# esp-firework-firing-system-hw1_1.net
KiCad netlist of a schematic drawn in EasyEDA
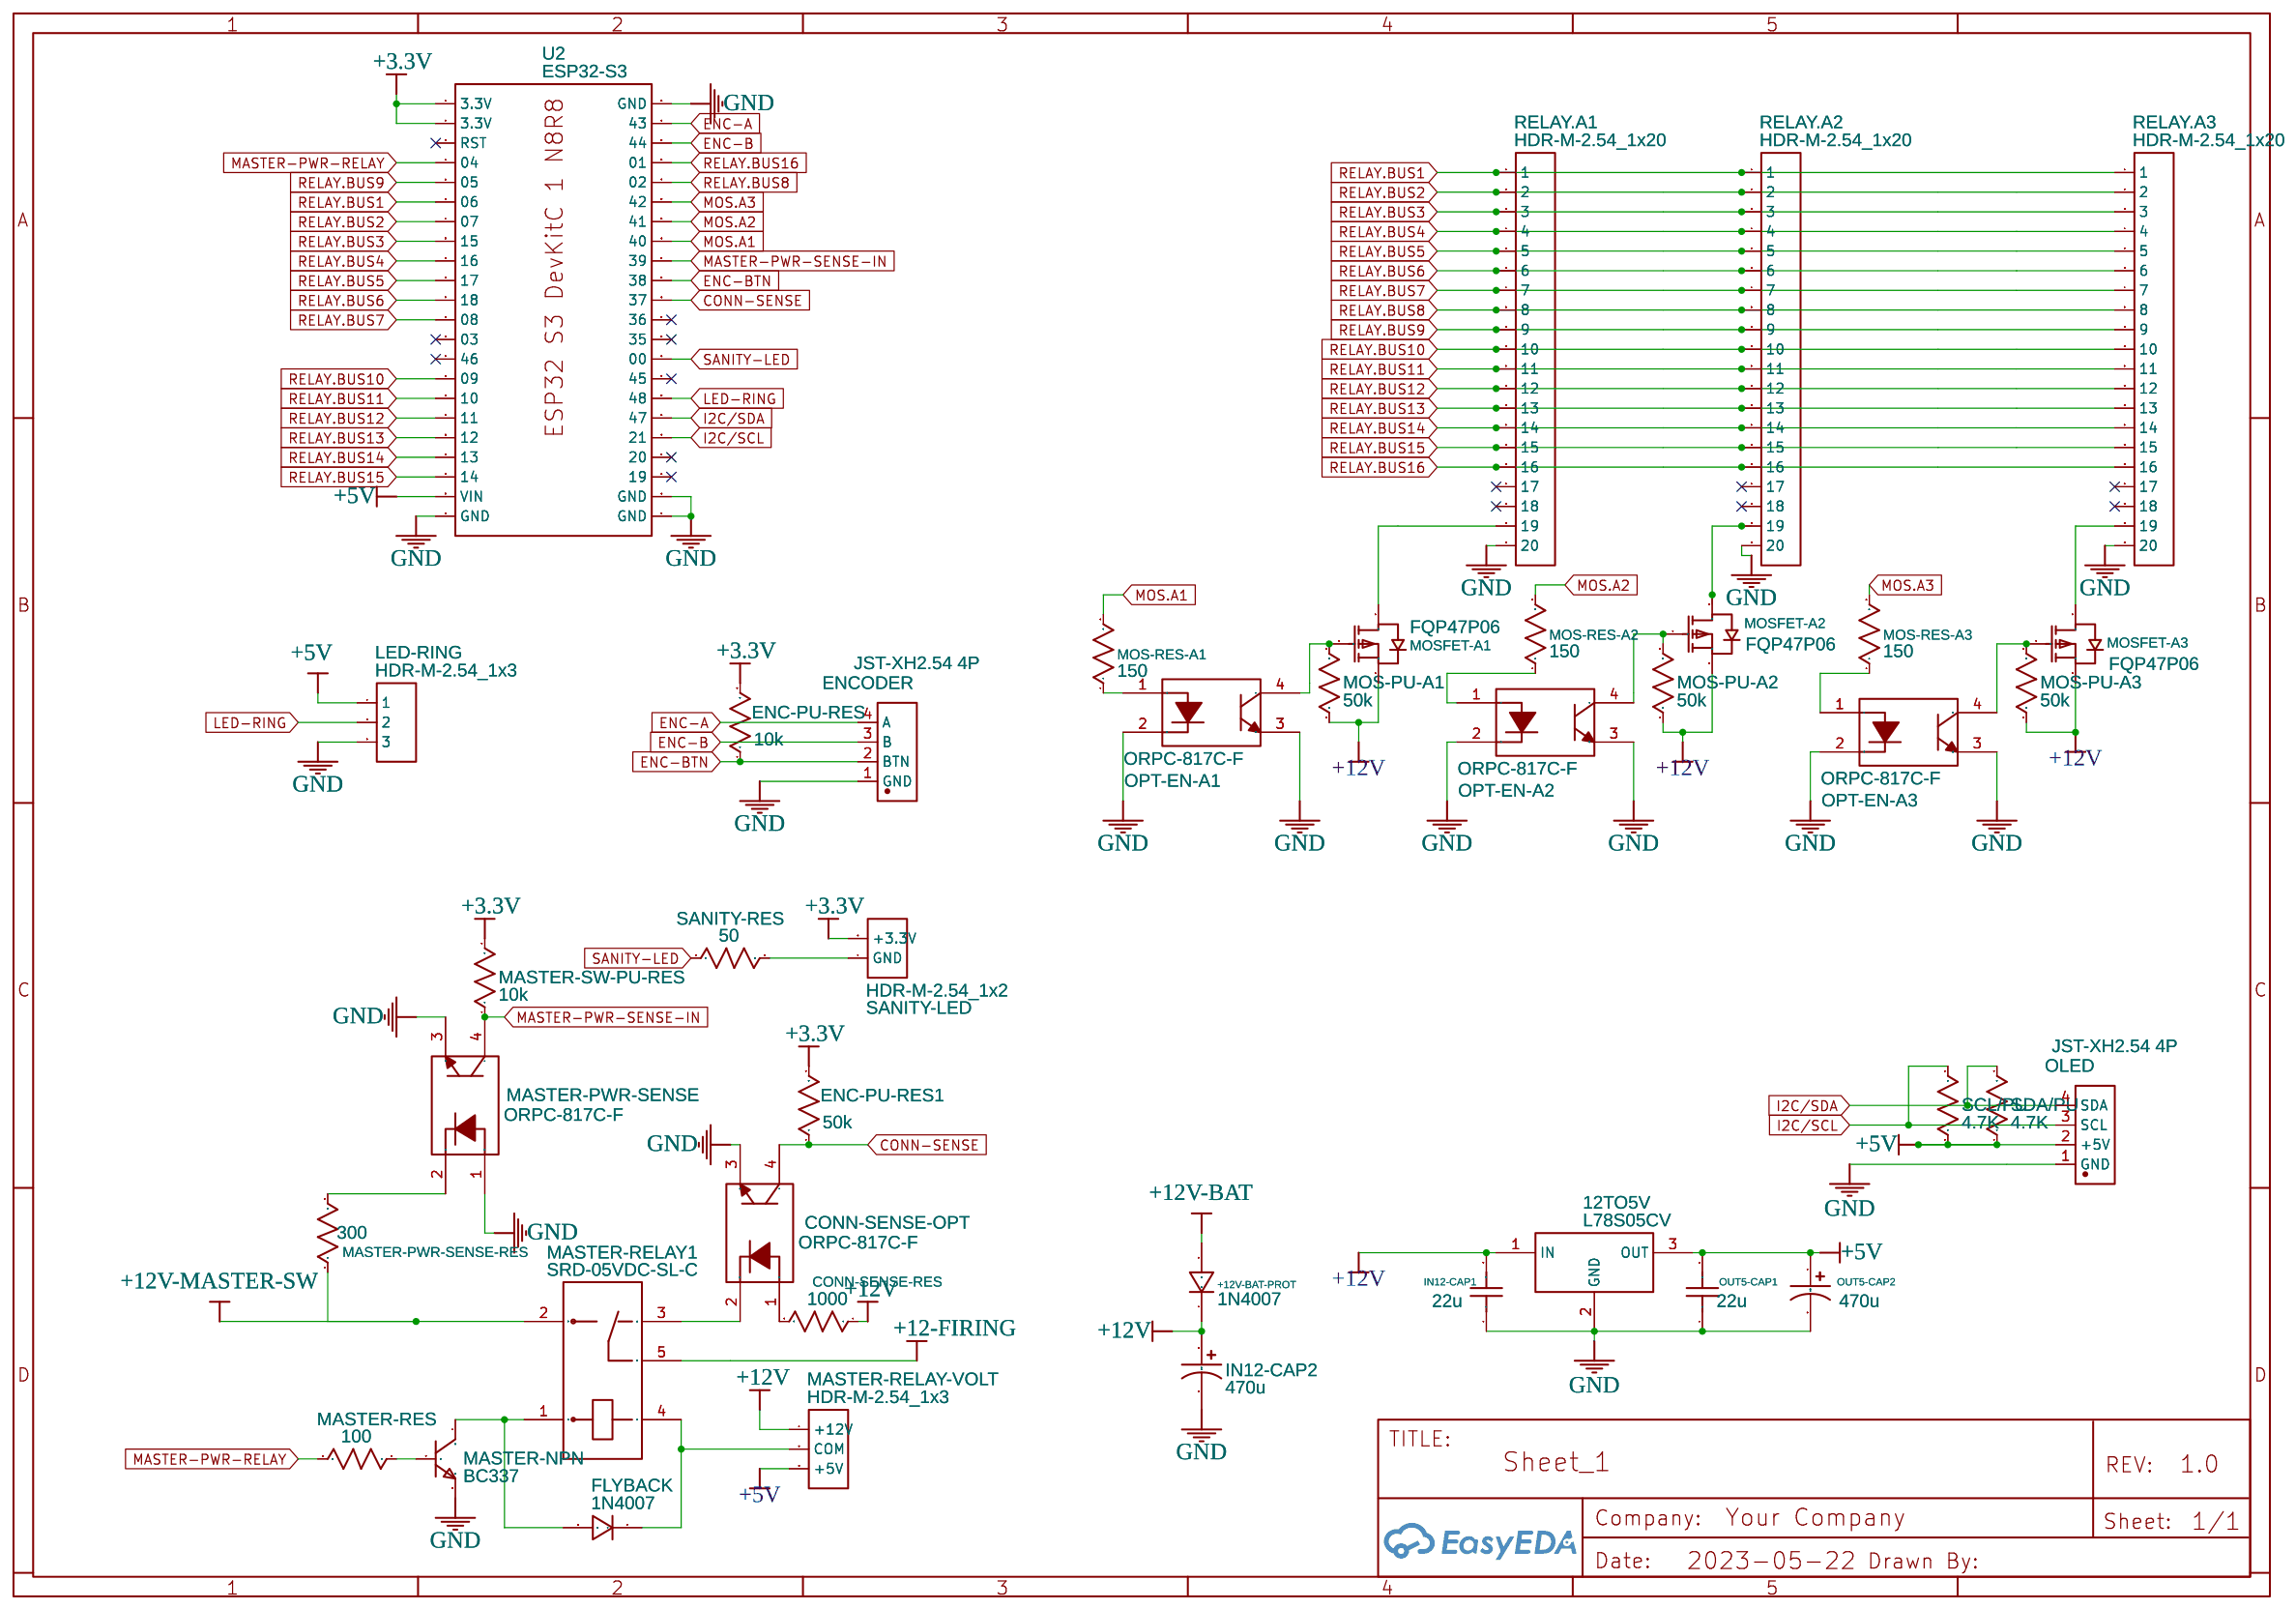
[diagram p0: schematic sheet]

(export (version "E")
  (design (tool "Eeschema 10.0.6"))
  (components
    (comp (ref "+12V-BAT-PROT")
      (value "1N4007")
      (fields (field (name "BOM_Supplier Part") "C106903"))
      (libsource (lib "") (part "1N4007_1"))
    )
    (comp (ref "12TO5V")
      (value "L78S05CV")
      (fields (field (name "BOM_Supplier Part") "C33043"))
      (libsource (lib "") (part "L78S05CV"))
    )
    (comp (ref "CONN-SENSE-OPT")
      (value "ORPC-817C-F")
      (fields (field (name "BOM_Supplier Part") "C2842770"))
      (libsource (lib "") (part "ORPC-817C-F_1"))
    )
    (comp (ref "CONN-SENSE-RES") (value "1000") (libsource (lib "") (part "R_AXIAL-0.3_US")))
    (comp (ref "ENC-PU-RES") (value "10k") (libsource (lib "") (part "R_AXIAL-0.3_US_3")))
    (comp (ref "ENC-PU-RES1") (value "50k") (libsource (lib "") (part "R_AXIAL-0.3_US_3")))
    (comp (ref "ENCODER") (value "JST-XH2.54 4P") (libsource (lib "") (part "JST-XH2.54 4P_1")))
    (comp (ref "FLYBACK")
      (value "1N4007")
      (fields (field (name "BOM_Supplier Part") "C106903"))
      (libsource (lib "") (part "1N4007"))
    )
    (comp (ref "IN12-CAP1") (value "22u") (libsource (lib "") (part "C_RAD-0.1_US_1")))
    (comp (ref "IN12-CAP2") (value "470u") (libsource (lib "") (part "CE_TH_D6.3×F2.5_US")))
    (comp (ref "LED-RING")
      (value "HDR-M-2.54_1x3")
      (fields (field (name "BOM_Supplier Part") "C180248"))
      (libsource (lib "") (part "HDR-M-2.54_1x3_1"))
    )
    (comp (ref "MASTER-NPN") (value "BC337") (libsource (lib "") (part "BC337")))
    (comp (ref "MASTER-PWR-SENSE")
      (value "ORPC-817C-F")
      (fields (field (name "BOM_Supplier Part") "C2842770"))
      (libsource (lib "") (part "ORPC-817C-F_2"))
    )
    (comp (ref "MASTER-PWR-SENSE-RES") (value "300") (libsource (lib "") (part "R_AXIAL-0.3_US_7")))
    (comp (ref "MASTER-RELAY-VOLT")
      (value "HDR-M-2.54_1x3")
      (fields (field (name "BOM_Supplier Part") "C180248"))
      (libsource (lib "") (part "HDR-M-2.54_1x3"))
    )
    (comp (ref "MASTER-RELAY1")
      (value "SRD-05VDC-SL-C")
      (fields (field (name "BOM_Supplier Part") "C35449"))
      (libsource (lib "") (part "SRD-05VDC-SL-C"))
    )
    (comp (ref "MASTER-RES") (value "100") (libsource (lib "") (part "R_AXIAL-0.3_US_6")))
    (comp (ref "MASTER-SW-PU-RES") (value "10k") (libsource (lib "") (part "R_AXIAL-0.3_US_1")))
    (comp (ref "MOS-PU-A1") (value "50k") (libsource (lib "") (part "R_AXIAL-0.3_US_2")))
    (comp (ref "MOS-PU-A2") (value "50k") (libsource (lib "") (part "R_AXIAL-0.3_US_2")))
    (comp (ref "MOS-PU-A3") (value "50k") (libsource (lib "") (part "R_AXIAL-0.3_US_2")))
    (comp (ref "MOS-RES-A1") (value "150") (libsource (lib "") (part "R_AXIAL-0.3_US_5")))
    (comp (ref "MOS-RES-A2") (value "150") (libsource (lib "") (part "R_AXIAL-0.3_US_5")))
    (comp (ref "MOS-RES-A3") (value "150") (libsource (lib "") (part "R_AXIAL-0.3_US_5")))
    (comp (ref "MOSFET-A1")
      (value "FQP47P06")
      (fields (field (name "BOM_Supplier Part") "C462765"))
      (libsource (lib "") (part "FQP47P06"))
    )
    (comp (ref "MOSFET-A2")
      (value "FQP47P06")
      (fields (field (name "BOM_Supplier Part") "C462765"))
      (libsource (lib "") (part "FQP47P06"))
    )
    (comp (ref "MOSFET-A3")
      (value "FQP47P06")
      (fields (field (name "BOM_Supplier Part") "C462765"))
      (libsource (lib "") (part "FQP47P06"))
    )
    (comp (ref "OLED") (value "JST-XH2.54 4P") (libsource (lib "") (part "JST-XH2.54 4P")))
    (comp (ref "OPT-EN-A1")
      (value "ORPC-817C-F")
      (fields (field (name "BOM_Supplier Part") "C2842770"))
      (libsource (lib "") (part "ORPC-817C-F"))
    )
    (comp (ref "OPT-EN-A2")
      (value "ORPC-817C-F")
      (fields (field (name "BOM_Supplier Part") "C2842770"))
      (libsource (lib "") (part "ORPC-817C-F"))
    )
    (comp (ref "OPT-EN-A3")
      (value "ORPC-817C-F")
      (fields (field (name "BOM_Supplier Part") "C2842770"))
      (libsource (lib "") (part "ORPC-817C-F"))
    )
    (comp (ref "OUT5-CAP1") (value "22u") (libsource (lib "") (part "C_RAD-0.1_US")))
    (comp (ref "OUT5-CAP2") (value "470u") (libsource (lib "") (part "CE_TH_D6.3×F2.5_US_1")))
    (comp (ref "RELAY.A1")
      (value "HDR-M-2.54_1x20")
      (fields (field (name "BOM_Supplier Part") "C50981"))
      (libsource (lib "") (part "HDR-M-2.54_1x20"))
    )
    (comp (ref "RELAY.A2")
      (value "HDR-M-2.54_1x20")
      (fields (field (name "BOM_Supplier Part") "C50981"))
      (libsource (lib "") (part "HDR-M-2.54_1x20"))
    )
    (comp (ref "RELAY.A3")
      (value "HDR-M-2.54_1x20")
      (fields (field (name "BOM_Supplier Part") "C50981"))
      (libsource (lib "") (part "HDR-M-2.54_1x20"))
    )
    (comp (ref "SANITY-LED")
      (value "HDR-M-2.54_1x2")
      (fields (field (name "BOM_Supplier Part") "C124375"))
      (libsource (lib "") (part "HDR-M-2.54_1x2"))
    )
    (comp (ref "SANITY-RES") (value "50") (libsource (lib "") (part "R_AXIAL-0.3_US_9")))
    (comp (ref "SCL/PU") (value "4.7K") (libsource (lib "") (part "R_AXIAL-0.3_US_4")))
    (comp (ref "SDA/PU") (value "4.7K") (libsource (lib "") (part "R_AXIAL-0.3_US_8")))
    (comp (ref "U2") (value "ESP32-S3") (libsource (lib "") (part "ESP32-S3")))
  )
  (nets
    (net (code "1") (name "+3.3V") (class "Default")
      (node (ref "ENC-PU-RES") (pin "2") (pinfunction "2_2") (pintype "unspecified"))
      (node (ref "ENC-PU-RES1") (pin "2") (pinfunction "2_2") (pintype "unspecified"))
      (node (ref "MASTER-SW-PU-RES") (pin "2") (pinfunction "2_2") (pintype "unspecified"))
      (node (ref "SANITY-LED") (pin "2") (pinfunction "+3.3V_2") (pintype "unspecified"))
      (node (ref "U2") (pin "1") (pinfunction "3.3V_1") (pintype "unspecified"))
      (node (ref "U2") (pin "2") (pinfunction "3.3V_2") (pintype "unspecified"))
    )
    (net (code "2") (name "+5V") (class "Default")
      (node (ref "12TO5V") (pin "3") (pinfunction "OUT_3") (pintype "passive"))
      (node (ref "LED-RING") (pin "1") (pinfunction "1_1") (pintype "input"))
      (node (ref "MASTER-RELAY-VOLT") (pin "3") (pinfunction "+5V_3") (pintype "input"))
      (node (ref "OLED") (pin "2") (pinfunction "+5V_2") (pintype "unspecified"))
      (node (ref "OUT5-CAP1") (pin "2") (pinfunction "2_2") (pintype "unspecified"))
      (node (ref "OUT5-CAP2") (pin "1") (pinfunction "1_1") (pintype "unspecified"))
      (node (ref "SCL/PU") (pin "1") (pinfunction "1_1") (pintype "unspecified"))
      (node (ref "SDA/PU") (pin "1") (pinfunction "1_1") (pintype "unspecified"))
      (node (ref "U2") (pin "21") (pinfunction "VIN_21") (pintype "unspecified"))
    )
    (net (code "3") (name "+12-FIRING") (class "Default")
      (node (ref "MASTER-RELAY1") (pin "5") (pinfunction "5_5") (pintype "input"))
    )
    (net (code "4") (name "+12V") (class "Default")
      (node (ref "+12V-BAT-PROT") (pin "1") (pinfunction "1_1") (pintype "unspecified"))
      (node (ref "12TO5V") (pin "1") (pinfunction "IN_1") (pintype "passive"))
      (node (ref "CONN-SENSE-RES") (pin "1") (pinfunction "1_1") (pintype "unspecified"))
      (node (ref "IN12-CAP1") (pin "2") (pinfunction "2_2") (pintype "unspecified"))
      (node (ref "IN12-CAP2") (pin "1") (pinfunction "1_1") (pintype "unspecified"))
      (node (ref "MASTER-RELAY-VOLT") (pin "1") (pinfunction "+12V_1") (pintype "input"))
      (node (ref "MOS-PU-A1") (pin "1") (pinfunction "1_1") (pintype "unspecified"))
      (node (ref "MOS-PU-A2") (pin "1") (pinfunction "1_1") (pintype "unspecified"))
      (node (ref "MOS-PU-A3") (pin "1") (pinfunction "1_1") (pintype "unspecified"))
      (node (ref "MOSFET-A1") (pin "3") (pinfunction "S_3") (pintype "unspecified"))
      (node (ref "MOSFET-A2") (pin "3") (pinfunction "S_3") (pintype "unspecified"))
      (node (ref "MOSFET-A3") (pin "3") (pinfunction "S_3") (pintype "unspecified"))
    )
    (net (code "5") (name "+12V-BAT") (class "Default")
      (node (ref "+12V-BAT-PROT") (pin "2") (pinfunction "2_2") (pintype "unspecified"))
    )
    (net (code "6") (name "+12V-MASTER-SW") (class "Default")
      (node (ref "MASTER-PWR-SENSE-RES") (pin "1") (pinfunction "1_1") (pintype "unspecified"))
      (node (ref "MASTER-RELAY1") (pin "2") (pinfunction "2_2") (pintype "input"))
    )
    (net (code "7") (name "CONN-SENSE") (class "Default")
      (node (ref "CONN-SENSE-OPT") (pin "4") (pinfunction "4_4") (pintype "unspecified"))
      (node (ref "ENC-PU-RES1") (pin "1") (pinfunction "1_1") (pintype "unspecified"))
      (node (ref "U2") (pin "33") (pinfunction "37_33") (pintype "unspecified"))
    )
    (net (code "8") (name "ENC-A") (class "Default")
      (node (ref "ENCODER") (pin "4") (pinfunction "A_4") (pintype "unspecified"))
      (node (ref "U2") (pin "24") (pinfunction "43_24") (pintype "unspecified"))
    )
    (net (code "9") (name "ENC-B") (class "Default")
      (node (ref "ENCODER") (pin "3") (pinfunction "B_3") (pintype "unspecified"))
      (node (ref "U2") (pin "25") (pinfunction "44_25") (pintype "unspecified"))
    )
    (net (code "10") (name "ENC-BTN") (class "Default")
      (node (ref "ENC-PU-RES") (pin "1") (pinfunction "1_1") (pintype "unspecified"))
      (node (ref "ENCODER") (pin "2") (pinfunction "BTN_2") (pintype "unspecified"))
      (node (ref "U2") (pin "32") (pinfunction "38_32") (pintype "unspecified"))
    )
    (net (code "11") (name "GND") (class "Default")
      (node (ref "12TO5V") (pin "2") (pinfunction "GND_2") (pintype "passive"))
      (node (ref "CONN-SENSE-OPT") (pin "3") (pinfunction "3_3") (pintype "unspecified"))
      (node (ref "ENCODER") (pin "1") (pinfunction "GND_1") (pintype "unspecified"))
      (node (ref "IN12-CAP1") (pin "1") (pinfunction "1_1") (pintype "unspecified"))
      (node (ref "IN12-CAP2") (pin "2") (pinfunction "2_2") (pintype "unspecified"))
      (node (ref "LED-RING") (pin "3") (pinfunction "3_3") (pintype "input"))
      (node (ref "MASTER-NPN") (pin "3") (pinfunction "E_3") (pintype "unspecified"))
      (node (ref "MASTER-PWR-SENSE") (pin "1") (pinfunction "1_1") (pintype "unspecified"))
      (node (ref "MASTER-PWR-SENSE") (pin "3") (pinfunction "3_3") (pintype "unspecified"))
      (node (ref "OLED") (pin "1") (pinfunction "GND_1") (pintype "unspecified"))
      (node (ref "OPT-EN-A1") (pin "2") (pinfunction "2_2") (pintype "unspecified"))
      (node (ref "OPT-EN-A1") (pin "3") (pinfunction "3_3") (pintype "unspecified"))
      (node (ref "OPT-EN-A2") (pin "2") (pinfunction "2_2") (pintype "unspecified"))
      (node (ref "OPT-EN-A2") (pin "3") (pinfunction "3_3") (pintype "unspecified"))
      (node (ref "OPT-EN-A3") (pin "2") (pinfunction "2_2") (pintype "unspecified"))
      (node (ref "OPT-EN-A3") (pin "3") (pinfunction "3_3") (pintype "unspecified"))
      (node (ref "OUT5-CAP1") (pin "1") (pinfunction "1_1") (pintype "unspecified"))
      (node (ref "OUT5-CAP2") (pin "2") (pinfunction "2_2") (pintype "unspecified"))
      (node (ref "RELAY.A1") (pin "20") (pinfunction "20_20") (pintype "unspecified"))
      (node (ref "RELAY.A2") (pin "20") (pinfunction "20_20") (pintype "unspecified"))
      (node (ref "RELAY.A3") (pin "20") (pinfunction "20_20") (pintype "unspecified"))
      (node (ref "U2") (pin "22") (pinfunction "GND_22") (pintype "unspecified"))
      (node (ref "U2") (pin "23") (pinfunction "GND_23") (pintype "unspecified"))
      (node (ref "U2") (pin "43") (pinfunction "GND_43") (pintype "unspecified"))
      (node (ref "U2") (pin "44") (pinfunction "GND_44") (pintype "unspecified"))
    )
    (net (code "12") (name "I2C{slash}SCL") (class "Default")
      (node (ref "OLED") (pin "3") (pinfunction "SCL_3") (pintype "unspecified"))
      (node (ref "SCL/PU") (pin "2") (pinfunction "2_2") (pintype "unspecified"))
      (node (ref "U2") (pin "40") (pinfunction "21_40") (pintype "unspecified"))
    )
    (net (code "13") (name "I2C{slash}SDA") (class "Default")
      (node (ref "OLED") (pin "4") (pinfunction "SDA_4") (pintype "unspecified"))
      (node (ref "SDA/PU") (pin "2") (pinfunction "2_2") (pintype "unspecified"))
      (node (ref "U2") (pin "39") (pinfunction "47_39") (pintype "unspecified"))
    )
    (net (code "14") (name "LED-RING") (class "Default")
      (node (ref "LED-RING") (pin "2") (pinfunction "2_2") (pintype "input"))
      (node (ref "U2") (pin "38") (pinfunction "48_38") (pintype "unspecified"))
    )
    (net (code "15") (name "MASTER-PWR-RELAY") (class "Default")
      (node (ref "MASTER-RES") (pin "2") (pinfunction "2_2") (pintype "unspecified"))
      (node (ref "U2") (pin "4") (pinfunction "04_4") (pintype "unspecified"))
    )
    (net (code "16") (name "MASTER-PWR-SENSE-IN") (class "Default")
      (node (ref "MASTER-PWR-SENSE") (pin "4") (pinfunction "4_4") (pintype "unspecified"))
      (node (ref "MASTER-SW-PU-RES") (pin "1") (pinfunction "1_1") (pintype "unspecified"))
      (node (ref "U2") (pin "31") (pinfunction "39_31") (pintype "unspecified"))
    )
    (net (code "17") (name "MOS.A1") (class "Default")
      (node (ref "MOS-RES-A1") (pin "2") (pinfunction "2_2") (pintype "unspecified"))
      (node (ref "U2") (pin "30") (pinfunction "40_30") (pintype "unspecified"))
    )
    (net (code "18") (name "MOS.A2") (class "Default")
      (node (ref "MOS-RES-A2") (pin "2") (pinfunction "2_2") (pintype "unspecified"))
      (node (ref "U2") (pin "29") (pinfunction "41_29") (pintype "unspecified"))
    )
    (net (code "19") (name "MOS.A3") (class "Default")
      (node (ref "MOS-RES-A3") (pin "2") (pinfunction "2_2") (pintype "unspecified"))
      (node (ref "U2") (pin "28") (pinfunction "42_28") (pintype "unspecified"))
    )
    (net (code "20") (name "Net-(CONN-SENSE-OPT-Pad1)") (class "Default")
      (node (ref "CONN-SENSE-OPT") (pin "1") (pinfunction "1_1") (pintype "unspecified"))
      (node (ref "CONN-SENSE-RES") (pin "2") (pinfunction "2_2") (pintype "unspecified"))
    )
    (net (code "21") (name "Net-(CONN-SENSE-OPT-Pad2)") (class "Default")
      (node (ref "CONN-SENSE-OPT") (pin "2") (pinfunction "2_2") (pintype "unspecified"))
      (node (ref "MASTER-RELAY1") (pin "3") (pinfunction "3_3") (pintype "input"))
    )
    (net (code "22") (name "Net-(MASTER-NPN-B)") (class "Default")
      (node (ref "MASTER-NPN") (pin "2") (pinfunction "B_2") (pintype "unspecified"))
      (node (ref "MASTER-RES") (pin "1") (pinfunction "1_1") (pintype "unspecified"))
    )
    (net (code "23") (name "Net-(MASTER-NPN-C)") (class "Default")
      (node (ref "FLYBACK") (pin "2") (pinfunction "2_2") (pintype "unspecified"))
      (node (ref "MASTER-NPN") (pin "1") (pinfunction "C_1") (pintype "unspecified"))
      (node (ref "MASTER-RELAY1") (pin "1") (pinfunction "1_1") (pintype "input"))
    )
    (net (code "24") (name "Net-(MASTER-PWR-SENSE-Pad2)") (class "Default")
      (node (ref "MASTER-PWR-SENSE") (pin "2") (pinfunction "2_2") (pintype "unspecified"))
      (node (ref "MASTER-PWR-SENSE-RES") (pin "2") (pinfunction "2_2") (pintype "unspecified"))
    )
    (net (code "25") (name "Net-(MASTER-RELAY-VOLT-COM)") (class "Default")
      (node (ref "FLYBACK") (pin "1") (pinfunction "1_1") (pintype "unspecified"))
      (node (ref "MASTER-RELAY-VOLT") (pin "2") (pinfunction "COM_2") (pintype "input"))
      (node (ref "MASTER-RELAY1") (pin "4") (pinfunction "4_4") (pintype "input"))
    )
    (net (code "26") (name "Net-(MOS-RES-A1-Pad1)") (class "Default")
      (node (ref "MOS-RES-A1") (pin "1") (pinfunction "1_1") (pintype "unspecified"))
      (node (ref "OPT-EN-A1") (pin "1") (pinfunction "1_1") (pintype "unspecified"))
    )
    (net (code "27") (name "Net-(MOS-RES-A2-Pad1)") (class "Default")
      (node (ref "MOS-RES-A2") (pin "1") (pinfunction "1_1") (pintype "unspecified"))
      (node (ref "OPT-EN-A2") (pin "1") (pinfunction "1_1") (pintype "unspecified"))
    )
    (net (code "28") (name "Net-(MOS-RES-A3-Pad1)") (class "Default")
      (node (ref "MOS-RES-A3") (pin "1") (pinfunction "1_1") (pintype "unspecified"))
      (node (ref "OPT-EN-A3") (pin "1") (pinfunction "1_1") (pintype "unspecified"))
    )
    (net (code "29") (name "Net-(MOSFET-A1-D)") (class "Default")
      (node (ref "MOSFET-A1") (pin "2") (pinfunction "D_2") (pintype "unspecified"))
      (node (ref "RELAY.A1") (pin "19") (pinfunction "19_19") (pintype "unspecified"))
    )
    (net (code "30") (name "Net-(MOSFET-A1-G)") (class "Default")
      (node (ref "MOS-PU-A1") (pin "2") (pinfunction "2_2") (pintype "unspecified"))
      (node (ref "MOSFET-A1") (pin "1") (pinfunction "G_1") (pintype "unspecified"))
      (node (ref "OPT-EN-A1") (pin "4") (pinfunction "4_4") (pintype "unspecified"))
    )
    (net (code "31") (name "Net-(MOSFET-A2-D)") (class "Default")
      (node (ref "MOSFET-A2") (pin "2") (pinfunction "D_2") (pintype "unspecified"))
      (node (ref "RELAY.A2") (pin "19") (pinfunction "19_19") (pintype "unspecified"))
    )
    (net (code "32") (name "Net-(MOSFET-A2-G)") (class "Default")
      (node (ref "MOS-PU-A2") (pin "2") (pinfunction "2_2") (pintype "unspecified"))
      (node (ref "MOSFET-A2") (pin "1") (pinfunction "G_1") (pintype "unspecified"))
      (node (ref "OPT-EN-A2") (pin "4") (pinfunction "4_4") (pintype "unspecified"))
    )
    (net (code "33") (name "Net-(MOSFET-A3-D)") (class "Default")
      (node (ref "MOSFET-A3") (pin "2") (pinfunction "D_2") (pintype "unspecified"))
      (node (ref "RELAY.A3") (pin "19") (pinfunction "19_19") (pintype "unspecified"))
    )
    (net (code "34") (name "Net-(MOSFET-A3-G)") (class "Default")
      (node (ref "MOS-PU-A3") (pin "2") (pinfunction "2_2") (pintype "unspecified"))
      (node (ref "MOSFET-A3") (pin "1") (pinfunction "G_1") (pintype "unspecified"))
      (node (ref "OPT-EN-A3") (pin "4") (pinfunction "4_4") (pintype "unspecified"))
    )
    (net (code "35") (name "Net-(SANITY-LED-GND)") (class "Default")
      (node (ref "SANITY-LED") (pin "1") (pinfunction "GND_1") (pintype "unspecified"))
      (node (ref "SANITY-RES") (pin "2") (pinfunction "2_2") (pintype "unspecified"))
    )
    (net (code "36") (name "RELAY.BUS1") (class "Default")
      (node (ref "RELAY.A1") (pin "1") (pinfunction "1_1") (pintype "unspecified"))
      (node (ref "RELAY.A2") (pin "1") (pinfunction "1_1") (pintype "unspecified"))
      (node (ref "RELAY.A3") (pin "1") (pinfunction "1_1") (pintype "unspecified"))
      (node (ref "U2") (pin "6") (pinfunction "06_6") (pintype "unspecified"))
    )
    (net (code "37") (name "RELAY.BUS2") (class "Default")
      (node (ref "RELAY.A1") (pin "2") (pinfunction "2_2") (pintype "unspecified"))
      (node (ref "RELAY.A2") (pin "2") (pinfunction "2_2") (pintype "unspecified"))
      (node (ref "RELAY.A3") (pin "2") (pinfunction "2_2") (pintype "unspecified"))
      (node (ref "U2") (pin "7") (pinfunction "07_7") (pintype "unspecified"))
    )
    (net (code "38") (name "RELAY.BUS3") (class "Default")
      (node (ref "RELAY.A1") (pin "3") (pinfunction "3_3") (pintype "unspecified"))
      (node (ref "RELAY.A2") (pin "3") (pinfunction "3_3") (pintype "unspecified"))
      (node (ref "RELAY.A3") (pin "3") (pinfunction "3_3") (pintype "unspecified"))
      (node (ref "U2") (pin "8") (pinfunction "15_8") (pintype "unspecified"))
    )
    (net (code "39") (name "RELAY.BUS4") (class "Default")
      (node (ref "RELAY.A1") (pin "4") (pinfunction "4_4") (pintype "unspecified"))
      (node (ref "RELAY.A2") (pin "4") (pinfunction "4_4") (pintype "unspecified"))
      (node (ref "RELAY.A3") (pin "4") (pinfunction "4_4") (pintype "unspecified"))
      (node (ref "U2") (pin "9") (pinfunction "16_9") (pintype "unspecified"))
    )
    (net (code "40") (name "RELAY.BUS5") (class "Default")
      (node (ref "RELAY.A1") (pin "5") (pinfunction "5_5") (pintype "unspecified"))
      (node (ref "RELAY.A2") (pin "5") (pinfunction "5_5") (pintype "unspecified"))
      (node (ref "RELAY.A3") (pin "5") (pinfunction "5_5") (pintype "unspecified"))
      (node (ref "U2") (pin "10") (pinfunction "17_10") (pintype "unspecified"))
    )
    (net (code "41") (name "RELAY.BUS6") (class "Default")
      (node (ref "RELAY.A1") (pin "6") (pinfunction "6_6") (pintype "unspecified"))
      (node (ref "RELAY.A2") (pin "6") (pinfunction "6_6") (pintype "unspecified"))
      (node (ref "RELAY.A3") (pin "6") (pinfunction "6_6") (pintype "unspecified"))
      (node (ref "U2") (pin "11") (pinfunction "18_11") (pintype "unspecified"))
    )
    (net (code "42") (name "RELAY.BUS7") (class "Default")
      (node (ref "RELAY.A1") (pin "7") (pinfunction "7_7") (pintype "unspecified"))
      (node (ref "RELAY.A2") (pin "7") (pinfunction "7_7") (pintype "unspecified"))
      (node (ref "RELAY.A3") (pin "7") (pinfunction "7_7") (pintype "unspecified"))
      (node (ref "U2") (pin "12") (pinfunction "08_12") (pintype "unspecified"))
    )
    (net (code "43") (name "RELAY.BUS8") (class "Default")
      (node (ref "RELAY.A1") (pin "8") (pinfunction "8_8") (pintype "unspecified"))
      (node (ref "RELAY.A2") (pin "8") (pinfunction "8_8") (pintype "unspecified"))
      (node (ref "RELAY.A3") (pin "8") (pinfunction "8_8") (pintype "unspecified"))
      (node (ref "U2") (pin "27") (pinfunction "02_27") (pintype "unspecified"))
    )
    (net (code "44") (name "RELAY.BUS9") (class "Default")
      (node (ref "RELAY.A1") (pin "9") (pinfunction "9_9") (pintype "unspecified"))
      (node (ref "RELAY.A2") (pin "9") (pinfunction "9_9") (pintype "unspecified"))
      (node (ref "RELAY.A3") (pin "9") (pinfunction "9_9") (pintype "unspecified"))
      (node (ref "U2") (pin "5") (pinfunction "05_5") (pintype "unspecified"))
    )
    (net (code "45") (name "RELAY.BUS10") (class "Default")
      (node (ref "RELAY.A1") (pin "10") (pinfunction "10_10") (pintype "unspecified"))
      (node (ref "RELAY.A2") (pin "10") (pinfunction "10_10") (pintype "unspecified"))
      (node (ref "RELAY.A3") (pin "10") (pinfunction "10_10") (pintype "unspecified"))
      (node (ref "U2") (pin "15") (pinfunction "09_15") (pintype "unspecified"))
    )
    (net (code "46") (name "RELAY.BUS11") (class "Default")
      (node (ref "RELAY.A1") (pin "11") (pinfunction "11_11") (pintype "unspecified"))
      (node (ref "RELAY.A2") (pin "11") (pinfunction "11_11") (pintype "unspecified"))
      (node (ref "RELAY.A3") (pin "11") (pinfunction "11_11") (pintype "unspecified"))
      (node (ref "U2") (pin "16") (pinfunction "10_16") (pintype "unspecified"))
    )
    (net (code "47") (name "RELAY.BUS12") (class "Default")
      (node (ref "RELAY.A1") (pin "12") (pinfunction "12_12") (pintype "unspecified"))
      (node (ref "RELAY.A2") (pin "12") (pinfunction "12_12") (pintype "unspecified"))
      (node (ref "RELAY.A3") (pin "12") (pinfunction "12_12") (pintype "unspecified"))
      (node (ref "U2") (pin "17") (pinfunction "11_17") (pintype "unspecified"))
    )
    (net (code "48") (name "RELAY.BUS13") (class "Default")
      (node (ref "RELAY.A1") (pin "13") (pinfunction "13_13") (pintype "unspecified"))
      (node (ref "RELAY.A2") (pin "13") (pinfunction "13_13") (pintype "unspecified"))
      (node (ref "RELAY.A3") (pin "13") (pinfunction "13_13") (pintype "unspecified"))
      (node (ref "U2") (pin "18") (pinfunction "12_18") (pintype "unspecified"))
    )
    (net (code "49") (name "RELAY.BUS14") (class "Default")
      (node (ref "RELAY.A1") (pin "14") (pinfunction "14_14") (pintype "unspecified"))
      (node (ref "RELAY.A2") (pin "14") (pinfunction "14_14") (pintype "unspecified"))
      (node (ref "RELAY.A3") (pin "14") (pinfunction "14_14") (pintype "unspecified"))
      (node (ref "U2") (pin "19") (pinfunction "13_19") (pintype "unspecified"))
    )
    (net (code "50") (name "RELAY.BUS15") (class "Default")
      (node (ref "RELAY.A1") (pin "15") (pinfunction "15_15") (pintype "unspecified"))
      (node (ref "RELAY.A2") (pin "15") (pinfunction "15_15") (pintype "unspecified"))
      (node (ref "RELAY.A3") (pin "15") (pinfunction "15_15") (pintype "unspecified"))
      (node (ref "U2") (pin "20") (pinfunction "14_20") (pintype "unspecified"))
    )
    (net (code "51") (name "RELAY.BUS16") (class "Default")
      (node (ref "RELAY.A1") (pin "16") (pinfunction "16_16") (pintype "unspecified"))
      (node (ref "RELAY.A2") (pin "16") (pinfunction "16_16") (pintype "unspecified"))
      (node (ref "RELAY.A3") (pin "16") (pinfunction "16_16") (pintype "unspecified"))
      (node (ref "U2") (pin "26") (pinfunction "01_26") (pintype "unspecified"))
    )
    (net (code "52") (name "SANITY-LED") (class "Default")
      (node (ref "SANITY-RES") (pin "1") (pinfunction "1_1") (pintype "unspecified"))
      (node (ref "U2") (pin "36") (pinfunction "00_36") (pintype "unspecified"))
    )
    (net (code "53") (name "unconnected-(RELAY.A1-Pad17)") (class "Default")
      (node (ref "RELAY.A1") (pin "17") (pinfunction "17_17") (pintype "unspecified+no_connect"))
    )
    (net (code "54") (name "unconnected-(RELAY.A1-Pad18)") (class "Default")
      (node (ref "RELAY.A1") (pin "18") (pinfunction "18_18") (pintype "unspecified+no_connect"))
    )
    (net (code "55") (name "unconnected-(RELAY.A2-Pad17)") (class "Default")
      (node (ref "RELAY.A2") (pin "17") (pinfunction "17_17") (pintype "unspecified+no_connect"))
    )
    (net (code "56") (name "unconnected-(RELAY.A2-Pad18)") (class "Default")
      (node (ref "RELAY.A2") (pin "18") (pinfunction "18_18") (pintype "unspecified+no_connect"))
    )
    (net (code "57") (name "unconnected-(RELAY.A3-Pad17)") (class "Default")
      (node (ref "RELAY.A3") (pin "17") (pinfunction "17_17") (pintype "unspecified+no_connect"))
    )
    (net (code "58") (name "unconnected-(RELAY.A3-Pad18)") (class "Default")
      (node (ref "RELAY.A3") (pin "18") (pinfunction "18_18") (pintype "unspecified+no_connect"))
    )
    (net (code "59") (name "unconnected-(U2-03-Pad13)") (class "Default")
      (node (ref "U2") (pin "13") (pinfunction "03_13") (pintype "unspecified+no_connect"))
    )
    (net (code "60") (name "unconnected-(U2-19-Pad42)") (class "Default")
      (node (ref "U2") (pin "42") (pinfunction "19_42") (pintype "unspecified+no_connect"))
    )
    (net (code "61") (name "unconnected-(U2-20-Pad41)") (class "Default")
      (node (ref "U2") (pin "41") (pinfunction "20_41") (pintype "unspecified+no_connect"))
    )
    (net (code "62") (name "unconnected-(U2-36-Pad34)") (class "Default")
      (node (ref "U2") (pin "34") (pinfunction "36_34") (pintype "unspecified+no_connect"))
    )
    (net (code "63") (name "unconnected-(U2-45-Pad37)") (class "Default")
      (node (ref "U2") (pin "37") (pinfunction "45_37") (pintype "unspecified+no_connect"))
    )
    (net (code "64") (name "unconnected-(U2-46-Pad14)") (class "Default")
      (node (ref "U2") (pin "14") (pinfunction "46_14") (pintype "unspecified+no_connect"))
    )
    (net (code "65") (name "unconnected-(U2-Pad35)") (class "Default")
      (node (ref "U2") (pin "35") (pinfunction "35_35") (pintype "unspecified+no_connect"))
    )
    (net (code "66") (name "unconnected-(U2-RST-Pad3)") (class "Default")
      (node (ref "U2") (pin "3") (pinfunction "RST_3") (pintype "unspecified+no_connect"))
    )
  )
)
